# USB_French_Bar_2.net
KiCad netlist of a schematic drawn in EAGLE
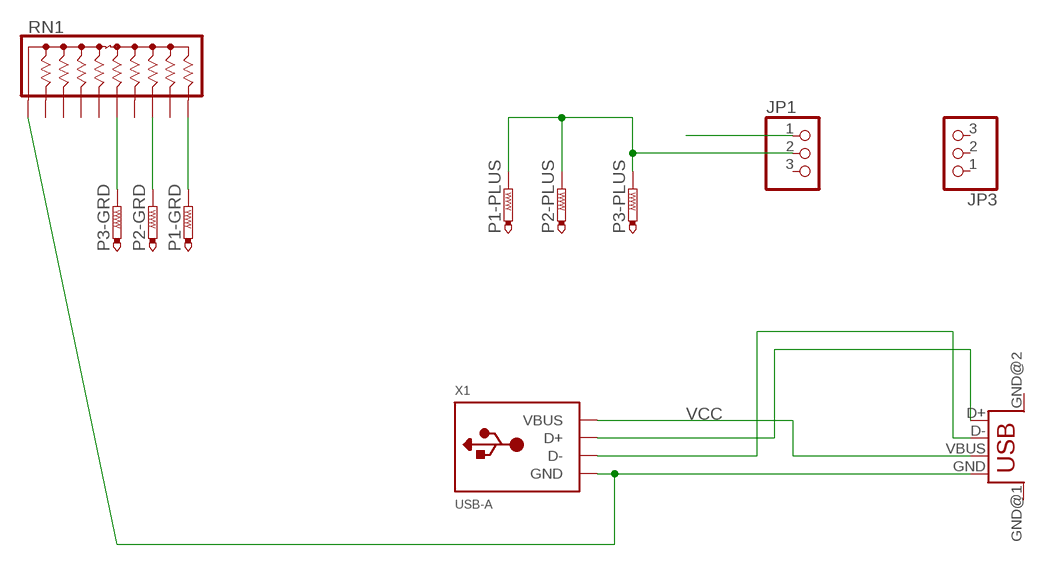
[diagram p0: schematic, sheet 1]

(export (version "E")
  (design (tool "Eeschema 10.0.6"))
  (components
    (comp (ref "JP1")
      (value "PINHD-1X3")
      (footprint "eagle-import:1X03")
      (libsource (lib "eagle-import") (part "PINHD-1X3"))
    )
    (comp (ref "JP3")
      (value "PINHD-1X3")
      (footprint "eagle-import:1X03")
      (libsource (lib "eagle-import") (part "PINHD-1X3"))
    )
    (comp (ref "P1-GRD")
      (value "PTR1TP20SQ")
      (footprint "eagle-import:TP20SQ")
      (libsource (lib "eagle-import") (part "PTR1TP20SQ"))
    )
    (comp (ref "P1-PLUS")
      (value "PTR1TP20SQ")
      (footprint "eagle-import:TP20SQ")
      (libsource (lib "eagle-import") (part "PTR1TP20SQ"))
    )
    (comp (ref "P2-GRD")
      (value "PTR1TP20SQ")
      (footprint "eagle-import:TP20SQ")
      (libsource (lib "eagle-import") (part "PTR1TP20SQ"))
    )
    (comp (ref "P2-PLUS")
      (value "PTR1TP20SQ")
      (footprint "eagle-import:TP20SQ")
      (libsource (lib "eagle-import") (part "PTR1TP20SQ"))
    )
    (comp (ref "P3-GRD")
      (value "PTR1TP20SQ")
      (footprint "eagle-import:TP20SQ")
      (libsource (lib "eagle-import") (part "PTR1TP20SQ"))
    )
    (comp (ref "P3-PLUS")
      (value "PTR1TP20SQ")
      (footprint "eagle-import:TP20SQ")
      (libsource (lib "eagle-import") (part "PTR1TP20SQ"))
    )
    (comp (ref "RN1")
      (value "4610X")
      (footprint "eagle-import:SIP10")
      (libsource (lib "eagle-import") (part "4610X"))
    )
    (comp (ref "U$1")
      (value "USB")
      (footprint "eagle-import:USB-FEMALE-A-PTH")
      (libsource (lib "eagle-import") (part "USB"))
    )
    (comp (ref "X1")
      (value "USB-A")
      (footprint "eagle-import:MOLEX_480371000")
      (libsource (lib "eagle-import") (part "USB-A"))
    )
  )
  (nets
    (net (code "1") (name "/VCC") (class "Default")
      (node (ref "JP1") (pin "1") (pinfunction "1_1") (pintype "passive"))
      (node (ref "U$1") (pin "VBUS") (pinfunction "VBUS_VBUS") (pintype "bidirectional"))
      (node (ref "X1") (pin "1") (pinfunction "VBUS_1") (pintype "power_in"))
    )
    (net (code "2") (name "Net-(JP1-Pad2)") (class "Default")
      (node (ref "JP1") (pin "2") (pinfunction "2_2") (pintype "passive"))
      (node (ref "P1-PLUS") (pin "TP") (pinfunction "TP_TP") (pintype "input"))
      (node (ref "P2-PLUS") (pin "TP") (pinfunction "TP_TP") (pintype "input"))
      (node (ref "P3-PLUS") (pin "TP") (pinfunction "TP_TP") (pintype "input"))
    )
    (net (code "3") (name "Net-(P1-GRD-PadTP)") (class "Default")
      (node (ref "P1-GRD") (pin "TP") (pinfunction "TP_TP") (pintype "input"))
      (node (ref "RN1") (pin "10") (pinfunction "10_10") (pintype "passive"))
    )
    (net (code "4") (name "Net-(P2-GRD-PadTP)") (class "Default")
      (node (ref "P2-GRD") (pin "TP") (pinfunction "TP_TP") (pintype "input"))
      (node (ref "RN1") (pin "8") (pinfunction "8_8") (pintype "passive"))
    )
    (net (code "5") (name "Net-(P3-GRD-PadTP)") (class "Default")
      (node (ref "P3-GRD") (pin "TP") (pinfunction "TP_TP") (pintype "input"))
      (node (ref "RN1") (pin "6") (pinfunction "6_6") (pintype "passive"))
    )
    (net (code "6") (name "Net-(X1-D+)") (class "Default")
      (node (ref "U$1") (pin "D+") (pinfunction "D+_D+") (pintype "bidirectional"))
      (node (ref "X1") (pin "3") (pinfunction "D+_3") (pintype "bidirectional"))
    )
    (net (code "7") (name "Net-(X1-D-)") (class "Default")
      (node (ref "U$1") (pin "D-") (pinfunction "D-_D-") (pintype "bidirectional"))
      (node (ref "X1") (pin "2") (pinfunction "D-_2") (pintype "bidirectional"))
    )
    (net (code "8") (name "Net-(X1-GND)") (class "Default")
      (node (ref "RN1") (pin "1") (pinfunction "1_1") (pintype "passive"))
      (node (ref "U$1") (pin "GND") (pinfunction "GND_GND") (pintype "bidirectional"))
      (node (ref "X1") (pin "4") (pinfunction "GND_4") (pintype "power_in"))
    )
    (net (code "9") (name "unconnected-(JP1-Pad3)") (class "Default")
      (node (ref "JP1") (pin "3") (pinfunction "3_3") (pintype "passive"))
    )
    (net (code "10") (name "unconnected-(JP3-Pad1)") (class "Default")
      (node (ref "JP3") (pin "1") (pinfunction "1_1") (pintype "passive"))
    )
    (net (code "11") (name "unconnected-(JP3-Pad2)") (class "Default")
      (node (ref "JP3") (pin "2") (pinfunction "2_2") (pintype "passive"))
    )
    (net (code "12") (name "unconnected-(JP3-Pad3)") (class "Default")
      (node (ref "JP3") (pin "3") (pinfunction "3_3") (pintype "passive"))
    )
    (net (code "13") (name "unconnected-(RN1-Pad2)") (class "Default")
      (node (ref "RN1") (pin "2") (pinfunction "2_2") (pintype "passive"))
    )
    (net (code "14") (name "unconnected-(RN1-Pad3)") (class "Default")
      (node (ref "RN1") (pin "3") (pinfunction "3_3") (pintype "passive"))
    )
    (net (code "15") (name "unconnected-(RN1-Pad4)") (class "Default")
      (node (ref "RN1") (pin "4") (pinfunction "4_4") (pintype "passive"))
    )
    (net (code "16") (name "unconnected-(RN1-Pad5)") (class "Default")
      (node (ref "RN1") (pin "5") (pinfunction "5_5") (pintype "passive"))
    )
    (net (code "17") (name "unconnected-(RN1-Pad7)") (class "Default")
      (node (ref "RN1") (pin "7") (pinfunction "7_7") (pintype "passive"))
    )
    (net (code "18") (name "unconnected-(RN1-Pad9)") (class "Default")
      (node (ref "RN1") (pin "9") (pinfunction "9_9") (pintype "passive"))
    )
    (net (code "19") (name "unconnected-(U$1-GND-PadGND@1)") (class "Default")
      (node (ref "U$1") (pin "GND@1") (pinfunction "GND_GND@1") (pintype "bidirectional"))
    )
    (net (code "20") (name "unconnected-(U$1-GND-PadGND@2)") (class "Default")
      (node (ref "U$1") (pin "GND@2") (pinfunction "GND_GND@2") (pintype "bidirectional"))
    )
  )
)
